# design.net
KiCad netlist of a schematic drawn in Altium Designer
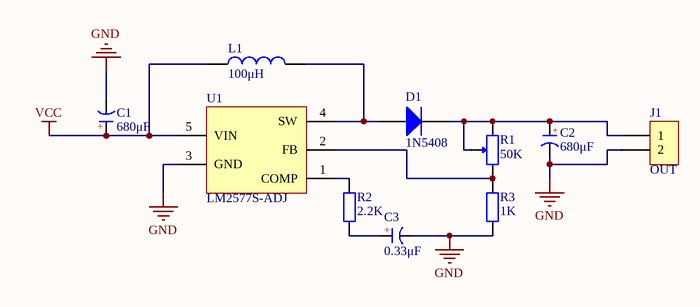
[diagram p0: 升压模块原理图.SchDoc]

(export (version "E")
  (design (tool "Eeschema 10.0.6"))
  (components
    (comp (ref "C1") (value "680μF") (libsource (lib "Schlib1") (part "极性电容")))
    (comp (ref "C2") (value "680μF") (libsource (lib "Schlib1") (part "极性电容")))
    (comp (ref "C3") (value "0.33μF") (libsource (lib "") (part "极性电容_1")))
    (comp (ref "D1")
      (value "1N5408")
      (footprint "DO-201AD")
      (description "3 Amp Medium Power Silicon Rectifier Diode")
      (fields (field (name "PUBLISHER") "Altium Limited"))
      (libsource (lib "Miscellaneous Devices") (part "Diode 1N5408"))
    )
    (comp (ref "J1")
      (value "OUT")
      (footprint "2PIN杜邦插座_1.27mm")
      (description "Connector")
      (libsource (lib "智能车主板") (part "CON2"))
    )
    (comp (ref "L1") (value "100μH") (libsource (lib "Schlib1") (part "电感")))
    (comp (ref "R1") (value "50K") (libsource (lib "Schlib1") (part "电位器")))
    (comp (ref "R2") (value "2.2K") (libsource (lib "Schlib1") (part "电阻")))
    (comp (ref "R3") (value "1K") (libsource (lib "Schlib1") (part "电阻")))
    (comp (ref "U1") (value "LM2577S-ADJ") (libsource (lib "Schlib1") (part "LM2577S-ADJ")))
  )
  (nets
    (net (code "1") (name "GND") (class "Default")
      (node (ref "C1") (pin "2") (pinfunction "K_2") (pintype "passive"))
      (node (ref "C2") (pin "2") (pinfunction "K_2") (pintype "passive"))
      (node (ref "C3") (pin "2") (pinfunction "K_2") (pintype "passive"))
      (node (ref "J1") (pin "2") (pinfunction "2_2") (pintype "passive"))
      (node (ref "R3") (pin "1") (pinfunction "1_1") (pintype "passive"))
      (node (ref "U1") (pin "3") (pinfunction "GND_3") (pintype "passive"))
    )
    (net (code "2") (name "Net-(C2-A)") (class "Default")
      (node (ref "C2") (pin "1") (pinfunction "A_1") (pintype "passive"))
      (node (ref "D1") (pin "2") (pinfunction "K_2") (pintype "passive"))
      (node (ref "J1") (pin "1") (pinfunction "1_1") (pintype "passive"))
      (node (ref "R1") (pin "2") (pinfunction "2_2") (pintype "passive"))
      (node (ref "R1") (pin "3") (pinfunction "3_3") (pintype "passive"))
    )
    (net (code "3") (name "Net-(C3-A)") (class "Default")
      (node (ref "C3") (pin "1") (pinfunction "A_1") (pintype "passive"))
      (node (ref "R2") (pin "1") (pinfunction "1_1") (pintype "passive"))
    )
    (net (code "4") (name "Net-(D1-A)") (class "Default")
      (node (ref "D1") (pin "1") (pinfunction "A_1") (pintype "passive"))
      (node (ref "L1") (pin "2") (pinfunction "2_2") (pintype "passive"))
      (node (ref "U1") (pin "4") (pinfunction "SW_4") (pintype "passive"))
    )
    (net (code "5") (name "Net-(U1-COMP)") (class "Default")
      (node (ref "R2") (pin "2") (pinfunction "2_2") (pintype "passive"))
      (node (ref "U1") (pin "1") (pinfunction "COMP_1") (pintype "passive"))
    )
    (net (code "6") (name "Net-(U1-FB)") (class "Default")
      (node (ref "R1") (pin "1") (pinfunction "1_1") (pintype "passive"))
      (node (ref "R3") (pin "2") (pinfunction "2_2") (pintype "passive"))
      (node (ref "U1") (pin "2") (pinfunction "FB_2") (pintype "passive"))
    )
    (net (code "7") (name "VCC") (class "Default")
      (node (ref "C1") (pin "1") (pinfunction "A_1") (pintype "passive"))
      (node (ref "L1") (pin "1") (pinfunction "1_1") (pintype "passive"))
      (node (ref "U1") (pin "5") (pinfunction "VIN_5") (pintype "passive"))
    )
  )
)
